# Pr_tica-04.net
KiCad netlist of a schematic drawn in EasyEDA
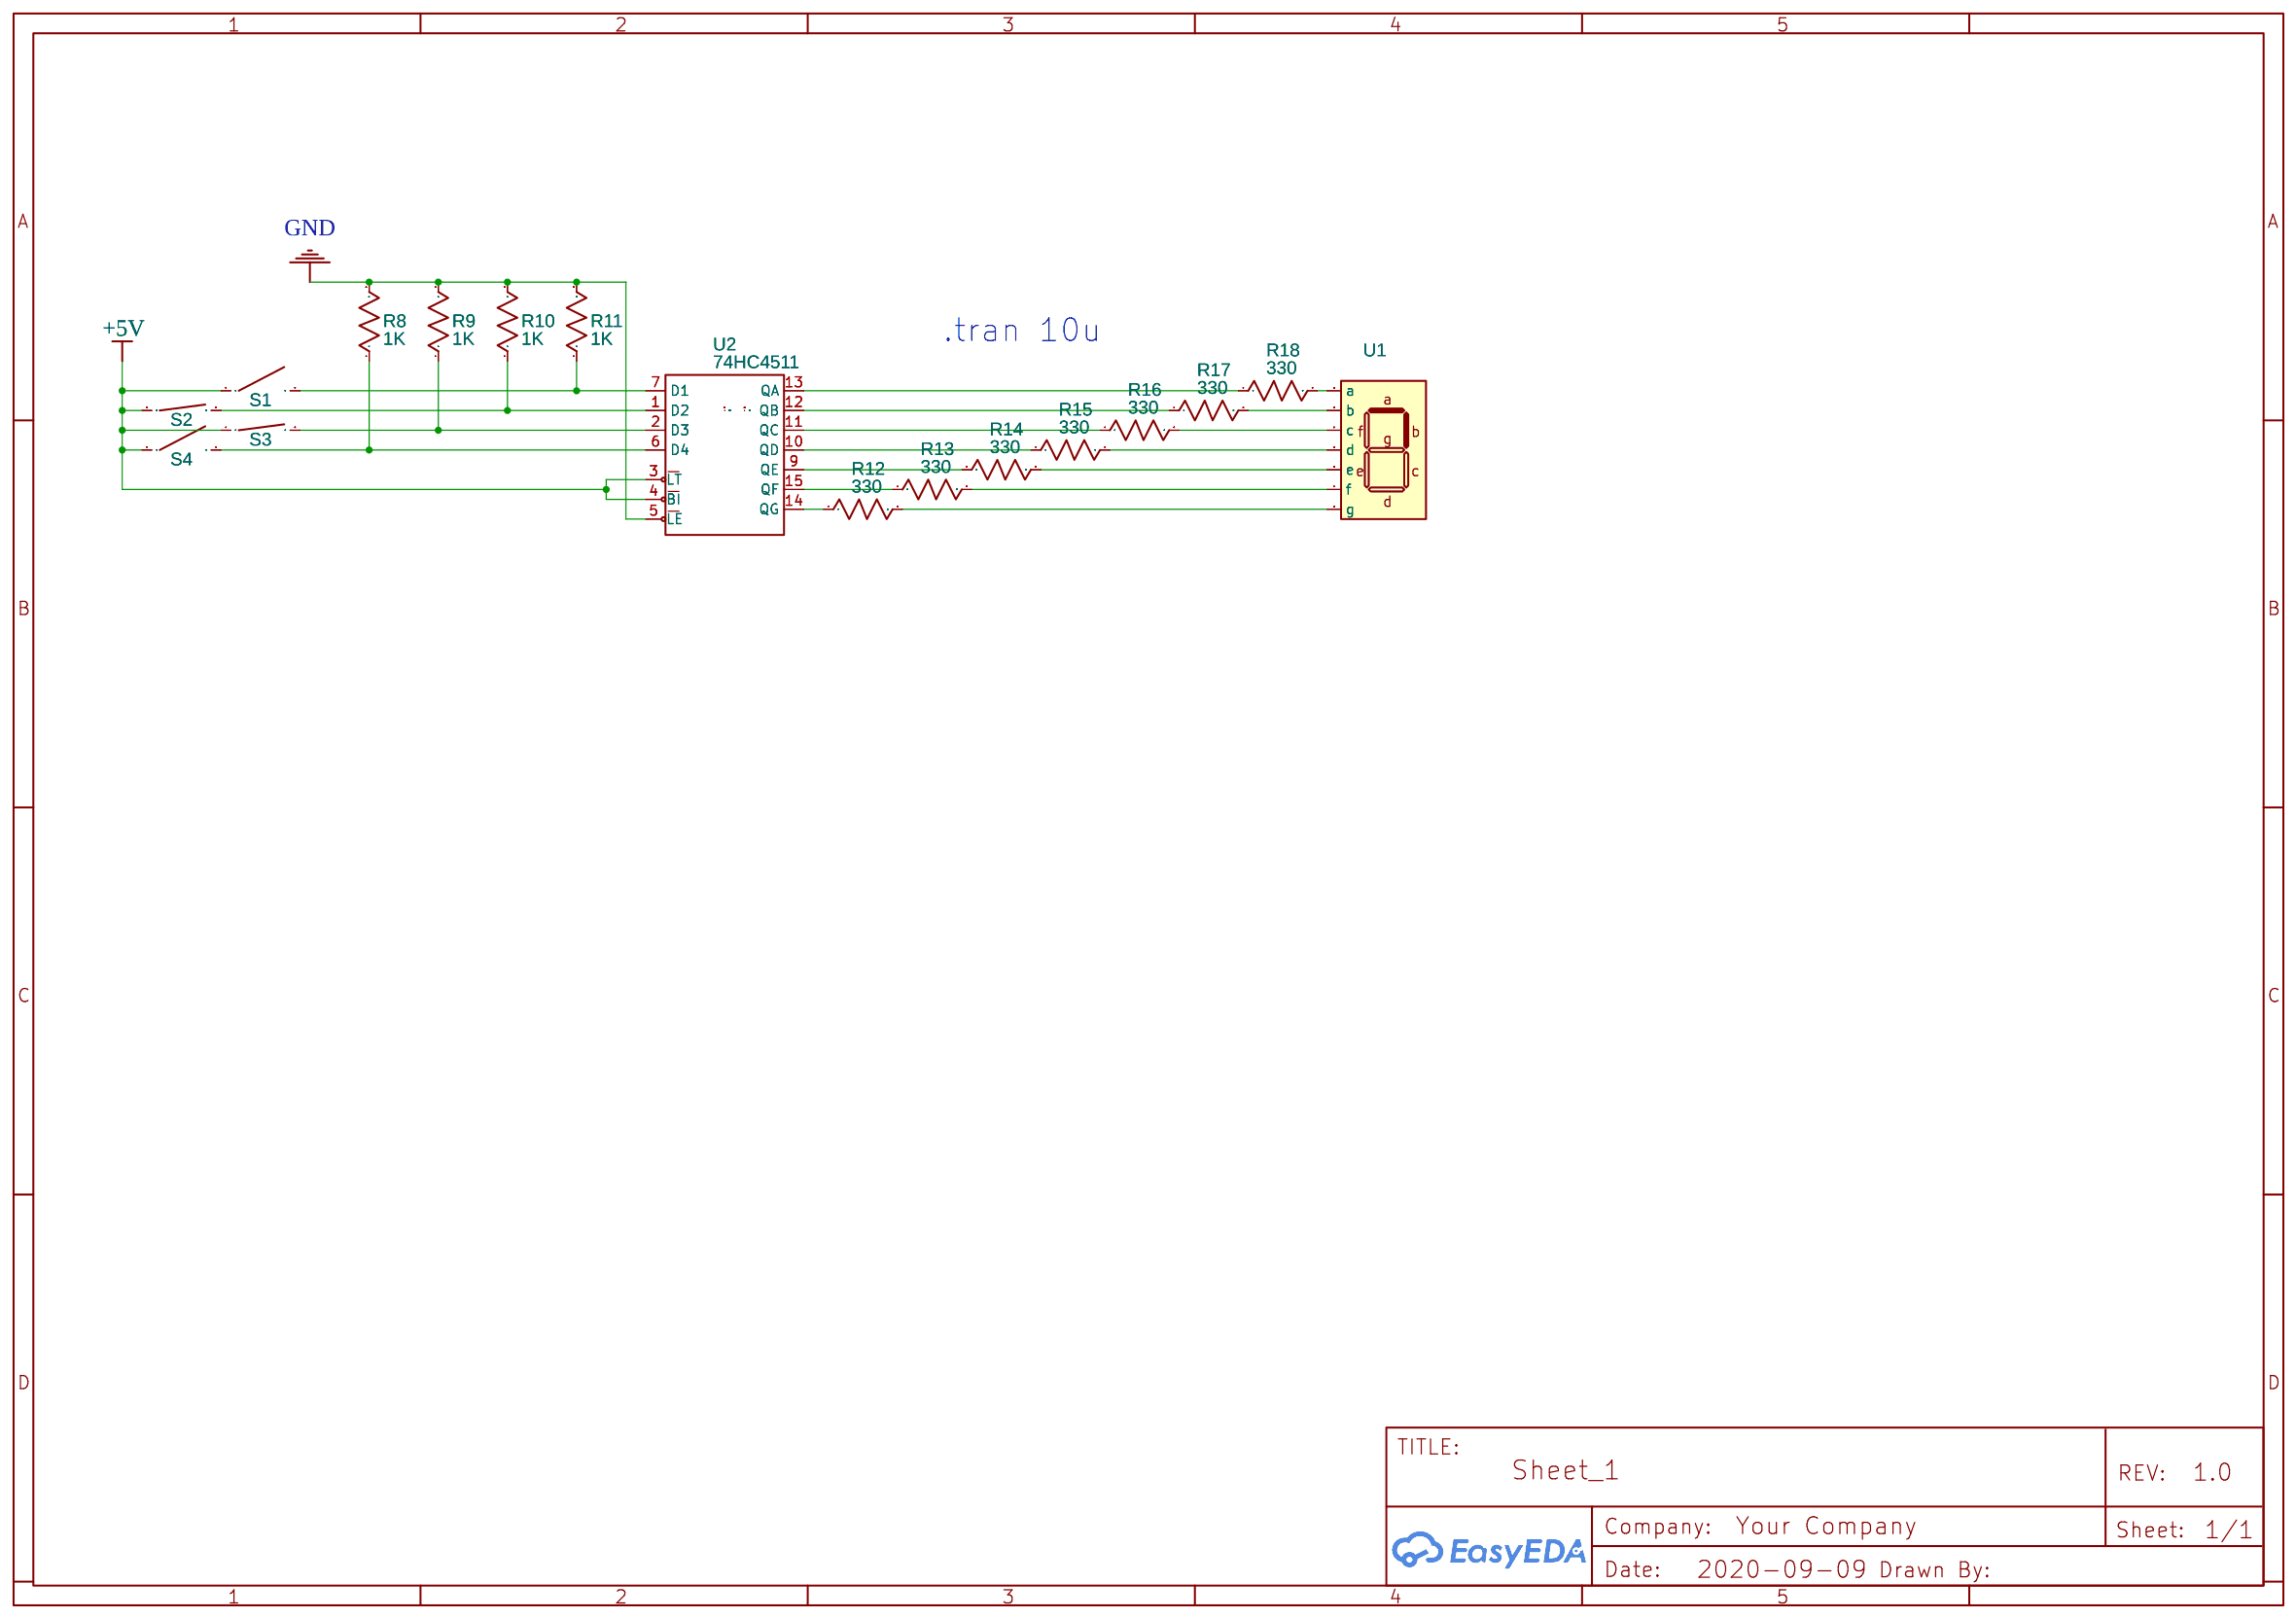
[diagram p0: schematic sheet]

(export (version "E")
  (design (tool "Eeschema 10.0.6"))
  (components
    (comp (ref "R8") (value "1K") (libsource (lib "") (part "Resistor_US_1")))
    (comp (ref "R9") (value "1K") (libsource (lib "") (part "Resistor_US_1")))
    (comp (ref "R10") (value "1K") (libsource (lib "") (part "Resistor_US_1")))
    (comp (ref "R11") (value "1K") (libsource (lib "") (part "Resistor_US_1")))
    (comp (ref "R12") (value "330") (libsource (lib "") (part "Resistor_US")))
    (comp (ref "R13") (value "330") (libsource (lib "") (part "Resistor_US")))
    (comp (ref "R14") (value "330") (libsource (lib "") (part "Resistor_US")))
    (comp (ref "R15") (value "330") (libsource (lib "") (part "Resistor_US")))
    (comp (ref "R16") (value "330") (libsource (lib "") (part "Resistor_US")))
    (comp (ref "R17") (value "330") (libsource (lib "") (part "Resistor_US")))
    (comp (ref "R18") (value "330") (libsource (lib "") (part "Resistor_US")))
    (comp (ref "S1") (value "SPST_Open") (libsource (lib "") (part "SPST")))
    (comp (ref "S2") (value "SPST_Open") (libsource (lib "") (part "SPST_1")))
    (comp (ref "S3") (value "SPST_Open") (libsource (lib "") (part "SPST_1")))
    (comp (ref "S4") (value "SPST_Open") (libsource (lib "") (part "SPST")))
    (comp (ref "U1") (value "Seven_Segment") (libsource (lib "") (part "SEVENSEGMENT")))
    (comp (ref "U2") (value "74HC4511") (libsource (lib "") (part "DIGITAL")))
  )
  (nets
    (net (code "1") (name "+5V") (class "Default")
      (node (ref "S1") (pin "1") (pinfunction "1_1") (pintype "unspecified"))
      (node (ref "S2") (pin "1") (pinfunction "1_1") (pintype "unspecified"))
      (node (ref "S3") (pin "1") (pinfunction "1_1") (pintype "unspecified"))
      (node (ref "S4") (pin "1") (pinfunction "1_1") (pintype "unspecified"))
      (node (ref "U2") (pin "3") (pinfunction "LT_3") (pintype "unspecified"))
      (node (ref "U2") (pin "4") (pinfunction "BI_4") (pintype "unspecified"))
    )
    (net (code "2") (name "GND") (class "Default")
      (node (ref "R10") (pin "2") (pinfunction "2_2") (pintype "unspecified"))
      (node (ref "R11") (pin "2") (pinfunction "2_2") (pintype "unspecified"))
      (node (ref "R8") (pin "2") (pinfunction "2_2") (pintype "unspecified"))
      (node (ref "R9") (pin "2") (pinfunction "2_2") (pintype "unspecified"))
      (node (ref "U2") (pin "5") (pinfunction "LE_5") (pintype "unspecified"))
    )
    (net (code "3") (name "Net-(R12-Pad2)") (class "Default")
      (node (ref "R12") (pin "2") (pinfunction "2_2") (pintype "unspecified"))
      (node (ref "U1") (pin "g") (pinfunction "g_g") (pintype "unspecified"))
    )
    (net (code "4") (name "Net-(R13-Pad2)") (class "Default")
      (node (ref "R13") (pin "2") (pinfunction "2_2") (pintype "unspecified"))
      (node (ref "U1") (pin "f") (pinfunction "f_f") (pintype "unspecified"))
    )
    (net (code "5") (name "Net-(R14-Pad2)") (class "Default")
      (node (ref "R14") (pin "2") (pinfunction "2_2") (pintype "unspecified"))
      (node (ref "U1") (pin "e") (pinfunction "e_e") (pintype "unspecified"))
    )
    (net (code "6") (name "Net-(R15-Pad2)") (class "Default")
      (node (ref "R15") (pin "2") (pinfunction "2_2") (pintype "unspecified"))
      (node (ref "U1") (pin "d") (pinfunction "d_d") (pintype "unspecified"))
    )
    (net (code "7") (name "Net-(R16-Pad2)") (class "Default")
      (node (ref "R16") (pin "2") (pinfunction "2_2") (pintype "unspecified"))
      (node (ref "U1") (pin "c") (pinfunction "c_c") (pintype "unspecified"))
    )
    (net (code "8") (name "Net-(R17-Pad2)") (class "Default")
      (node (ref "R17") (pin "2") (pinfunction "2_2") (pintype "unspecified"))
      (node (ref "U1") (pin "b") (pinfunction "b_b") (pintype "unspecified"))
    )
    (net (code "9") (name "Net-(R18-Pad2)") (class "Default")
      (node (ref "R18") (pin "2") (pinfunction "2_2") (pintype "unspecified"))
      (node (ref "U1") (pin "a") (pinfunction "a_a") (pintype "unspecified"))
    )
    (net (code "10") (name "Net-(U2-D1)") (class "Default")
      (node (ref "R11") (pin "1") (pinfunction "1_1") (pintype "unspecified"))
      (node (ref "S1") (pin "2") (pinfunction "2_2") (pintype "unspecified"))
      (node (ref "U2") (pin "7") (pinfunction "D1_7") (pintype "unspecified"))
    )
    (net (code "11") (name "Net-(U2-D2)") (class "Default")
      (node (ref "R10") (pin "1") (pinfunction "1_1") (pintype "unspecified"))
      (node (ref "S2") (pin "2") (pinfunction "2_2") (pintype "unspecified"))
      (node (ref "U2") (pin "1") (pinfunction "D2_1") (pintype "unspecified"))
    )
    (net (code "12") (name "Net-(U2-D3)") (class "Default")
      (node (ref "R9") (pin "1") (pinfunction "1_1") (pintype "unspecified"))
      (node (ref "S3") (pin "2") (pinfunction "2_2") (pintype "unspecified"))
      (node (ref "U2") (pin "2") (pinfunction "D3_2") (pintype "unspecified"))
    )
    (net (code "13") (name "Net-(U2-D4)") (class "Default")
      (node (ref "R8") (pin "1") (pinfunction "1_1") (pintype "unspecified"))
      (node (ref "S4") (pin "2") (pinfunction "2_2") (pintype "unspecified"))
      (node (ref "U2") (pin "6") (pinfunction "D4_6") (pintype "unspecified"))
    )
    (net (code "14") (name "Net-(U2-QA)") (class "Default")
      (node (ref "R18") (pin "1") (pinfunction "1_1") (pintype "unspecified"))
      (node (ref "U2") (pin "13") (pinfunction "QA_13") (pintype "unspecified"))
    )
    (net (code "15") (name "Net-(U2-QB)") (class "Default")
      (node (ref "R17") (pin "1") (pinfunction "1_1") (pintype "unspecified"))
      (node (ref "U2") (pin "12") (pinfunction "QB_12") (pintype "unspecified"))
    )
    (net (code "16") (name "Net-(U2-QC)") (class "Default")
      (node (ref "R16") (pin "1") (pinfunction "1_1") (pintype "unspecified"))
      (node (ref "U2") (pin "11") (pinfunction "QC_11") (pintype "unspecified"))
    )
    (net (code "17") (name "Net-(U2-QD)") (class "Default")
      (node (ref "R15") (pin "1") (pinfunction "1_1") (pintype "unspecified"))
      (node (ref "U2") (pin "10") (pinfunction "QD_10") (pintype "unspecified"))
    )
    (net (code "18") (name "Net-(U2-QE)") (class "Default")
      (node (ref "R14") (pin "1") (pinfunction "1_1") (pintype "unspecified"))
      (node (ref "U2") (pin "9") (pinfunction "QE_9") (pintype "unspecified"))
    )
    (net (code "19") (name "Net-(U2-QF)") (class "Default")
      (node (ref "R13") (pin "1") (pinfunction "1_1") (pintype "unspecified"))
      (node (ref "U2") (pin "15") (pinfunction "QF_15") (pintype "unspecified"))
    )
    (net (code "20") (name "Net-(U2-QG)") (class "Default")
      (node (ref "R12") (pin "1") (pinfunction "1_1") (pintype "unspecified"))
      (node (ref "U2") (pin "14") (pinfunction "QG_14") (pintype "unspecified"))
    )
    (net (code "21") (name "unconnected-(U2-GND-Pad8)") (class "Default")
      (node (ref "U2") (pin "8") (pinfunction "GND_8") (pintype "unspecified"))
    )
    (net (code "22") (name "unconnected-(U2-VCC-Pad16)") (class "Default")
      (node (ref "U2") (pin "16") (pinfunction "VCC_16") (pintype "unspecified"))
    )
  )
)
